# rodentdbs.net
KiCad netlist of a schematic drawn in EAGLE
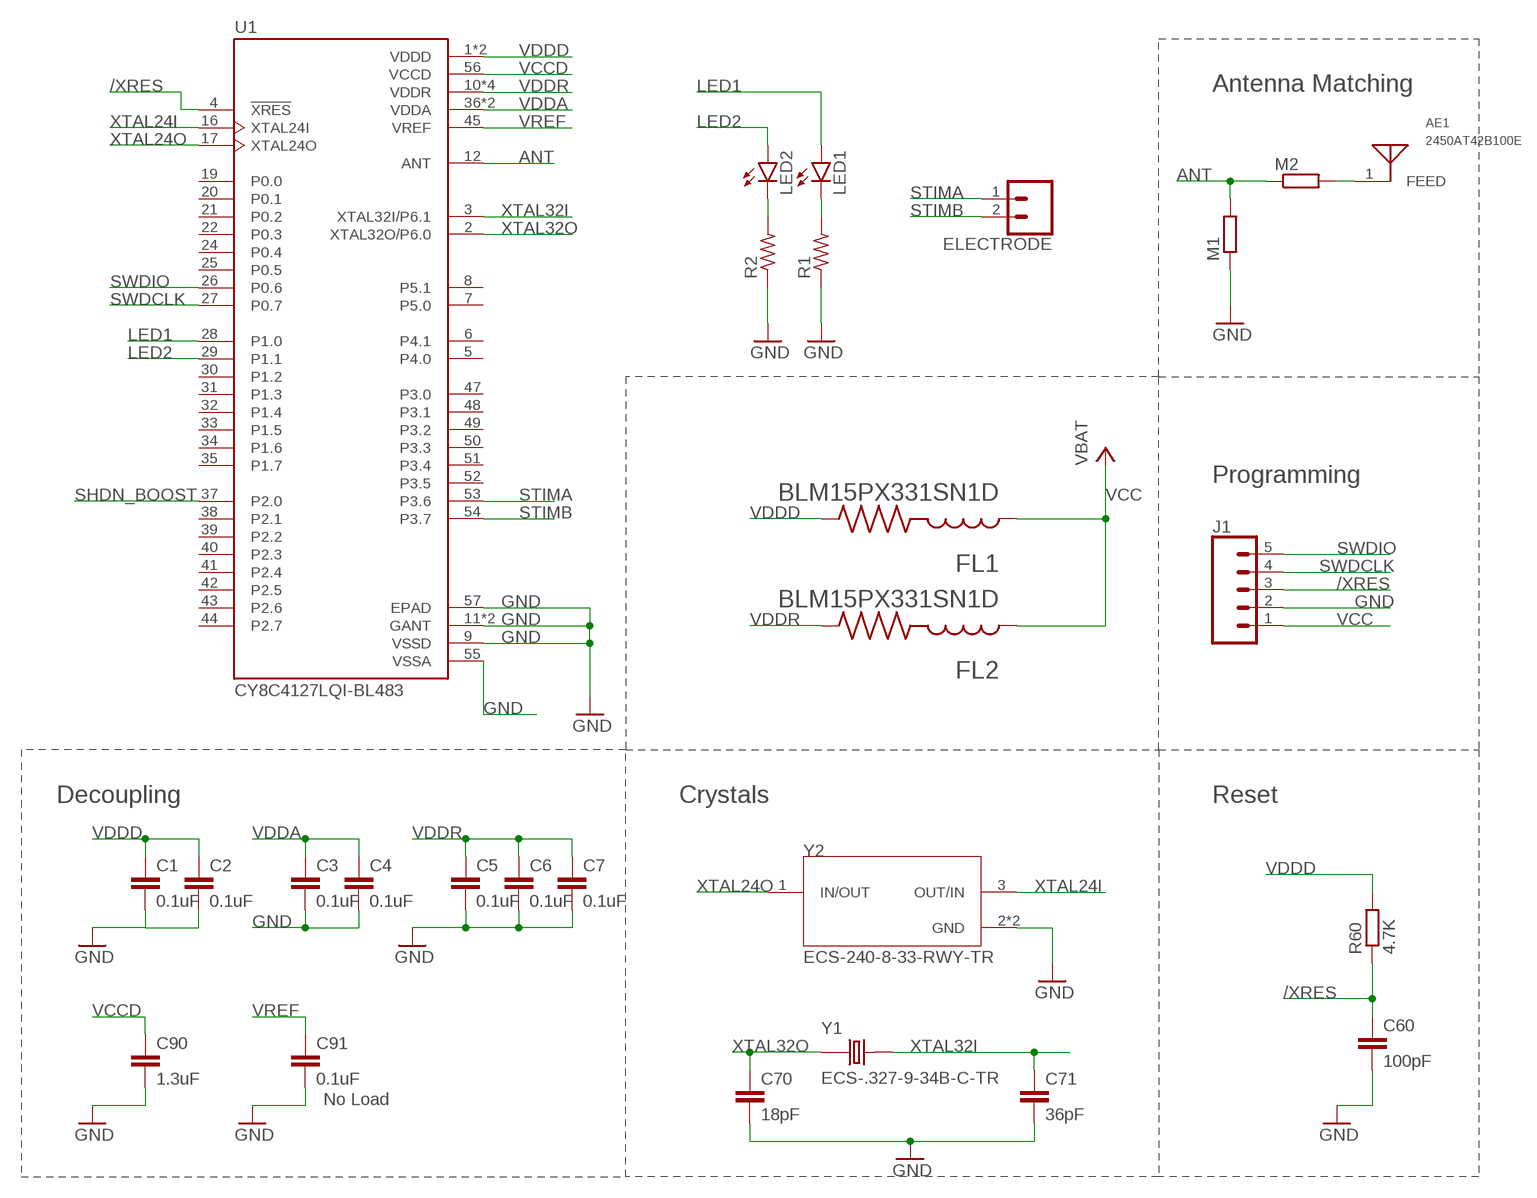
[diagram p0: schematic, sheet 1]
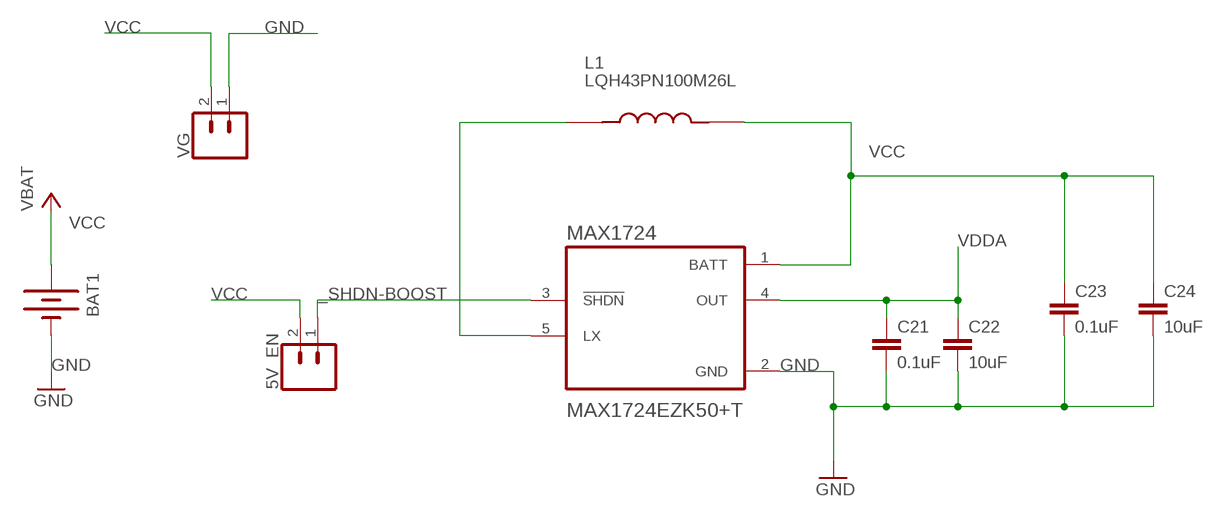
[diagram p1: schematic, sheet 2]

(export (version "E")
  (design (tool "Eeschema 10.0.6"))
  (components
    (comp (ref "AE1")
      (value "2450AT42B100E")
      (footprint "eagle-import:XCVR_2450AT42B100E")
      (fields (field (name "DIGI-KEY_PART_NUMBER") "712-1008-2-ND") (field (name "MF") "Johanson Technology"))
      (libsource (lib "eagle-import") (part "2450AT42B100E"))
    )
    (comp (ref "C1")
      (value "0.1uF")
      (footprint "eagle-import:C0402")
      (libsource (lib "eagle-import") (part "C-EUC0402"))
    )
    (comp (ref "C2")
      (value "0.1uF")
      (footprint "eagle-import:C0402")
      (libsource (lib "eagle-import") (part "C-EUC0402"))
    )
    (comp (ref "C3")
      (value "0.1uF")
      (footprint "eagle-import:C0402")
      (libsource (lib "eagle-import") (part "C-EUC0402"))
    )
    (comp (ref "C4")
      (value "0.1uF")
      (footprint "eagle-import:C0402")
      (libsource (lib "eagle-import") (part "C-EUC0402"))
    )
    (comp (ref "C5")
      (value "0.1uF")
      (footprint "eagle-import:C0402")
      (libsource (lib "eagle-import") (part "C-EUC0402"))
    )
    (comp (ref "C6")
      (value "0.1uF")
      (footprint "eagle-import:C0402")
      (libsource (lib "eagle-import") (part "C-EUC0402"))
    )
    (comp (ref "C7")
      (value "0.1uF")
      (footprint "eagle-import:C0402")
      (libsource (lib "eagle-import") (part "C-EUC0402"))
    )
    (comp (ref "C60")
      (value "100pF")
      (footprint "eagle-import:C0402")
      (libsource (lib "eagle-import") (part "C-EUC0402"))
    )
    (comp (ref "C70")
      (value "18pF")
      (footprint "eagle-import:C0402")
      (libsource (lib "eagle-import") (part "C-EUC0402"))
    )
    (comp (ref "C71")
      (value "36pF")
      (footprint "eagle-import:C0402")
      (libsource (lib "eagle-import") (part "C-EUC0402"))
    )
    (comp (ref "C90")
      (value "1.3uF")
      (footprint "eagle-import:C0402")
      (libsource (lib "eagle-import") (part "C-EUC0402"))
    )
    (comp (ref "C91")
      (value "0.1uF")
      (footprint "eagle-import:C0402")
      (libsource (lib "eagle-import") (part "C-EUC0402"))
    )
    (comp (ref "ELECTRODE")
      (value "CONN_02")
      (footprint "eagle-import:1X02")
      (libsource (lib "eagle-import") (part "CONN_02"))
    )
    (comp (ref "FL1")
      (value "BLM15PX331SN1D")
      (footprint "eagle-import:BEADC1005X55N")
      (fields (field (name "DIGI-KEY_PART_NUMBER") "490-11022-2-ND") (field (name "MF") "Murata Electronics"))
      (libsource (lib "eagle-import") (part "BLM15PX331SN1D"))
    )
    (comp (ref "FL2")
      (value "BLM15PX331SN1D")
      (footprint "eagle-import:BEADC1005X55N")
      (fields (field (name "DIGI-KEY_PART_NUMBER") "490-11022-2-ND") (field (name "MF") "Murata Electronics"))
      (libsource (lib "eagle-import") (part "BLM15PX331SN1D"))
    )
    (comp (ref "J1")
      (value "CONN_05LOCK")
      (footprint "eagle-import:1X05_LOCK")
      (libsource (lib "eagle-import") (part "CONN_05LOCK"))
    )
    (comp (ref "LED1")
      (value "LEDSML0603")
      (footprint "eagle-import:SML0603")
      (libsource (lib "eagle-import") (part "LEDSML0603"))
    )
    (comp (ref "LED2")
      (value "LEDSML0603")
      (footprint "eagle-import:SML0603")
      (libsource (lib "eagle-import") (part "LEDSML0603"))
    )
    (comp (ref "M1")
      (value "R-EU_R0402")
      (footprint "eagle-import:R0402")
      (libsource (lib "eagle-import") (part "R-EU_R0402"))
    )
    (comp (ref "M2")
      (value "R-EU_R0402")
      (footprint "eagle-import:R0402")
      (libsource (lib "eagle-import") (part "R-EU_R0402"))
    )
    (comp (ref "R1")
      (value "R-US_R0402")
      (footprint "eagle-import:R0402")
      (libsource (lib "eagle-import") (part "R-US_R0402"))
    )
    (comp (ref "R2")
      (value "R-US_R0402")
      (footprint "eagle-import:R0402")
      (libsource (lib "eagle-import") (part "R-US_R0402"))
    )
    (comp (ref "R60")
      (value "4.7K")
      (footprint "eagle-import:R0402")
      (libsource (lib "eagle-import") (part "R-EU_R0402"))
    )
    (comp (ref "U1")
      (value "CY8C4127LQI-BL483")
      (footprint "eagle-import:QFN40P700X700X60-57N")
      (libsource (lib "eagle-import") (part "CY8C4127LQI-BL483"))
    )
    (comp (ref "Y1")
      (value "ECS-.327-9-34B-C-TR")
      (footprint "eagle-import:XTAL_ECS-.327-9-34B-C-TR")
      (fields (field (name "DIGI-KEY_PART_NUMBER") "XC1949TR-ND") (field (name "MF") "ECS Inc."))
      (libsource (lib "eagle-import") (part "ECS-.327-9-34B-C-TR"))
    )
    (comp (ref "Y2")
      (value "ECS-240-8-33-RWY-TR")
      (footprint "eagle-import:XTAL_ECS-240-8-33-RWY-TR")
      (fields (field (name "DIGI-KEY_PART_NUMBER") "XC2946TR-ND") (field (name "MF") "ECS Inc."))
      (libsource (lib "eagle-import") (part "ECS-240-8-33-RWY-TR"))
    )
    (comp (ref "5V_EN")
      (value "CONN_02")
      (footprint "eagle-import:1X02")
      (libsource (lib "eagle-import") (part "CONN_02"))
    )
    (comp (ref "BAT1")
      (value "BATTERYBU2032SM")
      (footprint "eagle-import:BU2032SM")
      (libsource (lib "eagle-import") (part "BATTERYBU2032SM"))
    )
    (comp (ref "C21")
      (value "0.1uF")
      (footprint "eagle-import:C0402")
      (libsource (lib "eagle-import") (part "C-EUC0402"))
    )
    (comp (ref "C22")
      (value "10uF")
      (footprint "eagle-import:C0603")
      (libsource (lib "eagle-import") (part "C-EUC0603"))
    )
    (comp (ref "C23")
      (value "0.1uF")
      (footprint "eagle-import:C0402")
      (libsource (lib "eagle-import") (part "C-EUC0402"))
    )
    (comp (ref "C24")
      (value "10uF")
      (footprint "eagle-import:C0603")
      (libsource (lib "eagle-import") (part "C-EUC0603"))
    )
    (comp (ref "L1")
      (value "LQH43PN100M26L")
      (footprint "eagle-import:IND_LQH43PN100M26L")
      (fields (field (name "DIGI-KEY_PART_NUMBER") "490-12780-1-ND") (field (name "MF") "Murata"))
      (libsource (lib "eagle-import") (part "LQH43PN100M26L"))
    )
    (comp (ref "MAX1724")
      (value "MAX1724EZK50+T")
      (footprint "eagle-import:SOT95P275X110-5N")
      (fields
        (field (name "DIGI-KEY_PART_NUMBER") "MAX1724EZK50+TCT-ND")
        (field (name "MF") "Maxim Integrated")
      )
      (libsource (lib "eagle-import") (part "MAX1724EZK50+T"))
    )
    (comp (ref "VG")
      (value "CONN_02")
      (footprint "eagle-import:1X02")
      (libsource (lib "eagle-import") (part "CONN_02"))
    )
  )
  (nets
    (net (code "1") (name "ANT") (class "Default")
      (node (ref "M1") (pin "2") (pinfunction "2_2") (pintype "passive"))
      (node (ref "M2") (pin "1") (pinfunction "1_1") (pintype "passive"))
      (node (ref "U1") (pin "12") (pinfunction "ANT_12") (pintype "bidirectional"))
    )
    (net (code "2") (name "GND") (class "Default")
      (node (ref "BAT1") (pin "P$2") (pinfunction "-_P$2") (pintype "power_in"))
      (node (ref "C1") (pin "2") (pinfunction "2_2") (pintype "passive"))
      (node (ref "C2") (pin "2") (pinfunction "2_2") (pintype "passive"))
      (node (ref "C21") (pin "2") (pinfunction "2_2") (pintype "passive"))
      (node (ref "C22") (pin "2") (pinfunction "2_2") (pintype "passive"))
      (node (ref "C23") (pin "2") (pinfunction "2_2") (pintype "passive"))
      (node (ref "C24") (pin "2") (pinfunction "2_2") (pintype "passive"))
      (node (ref "C3") (pin "2") (pinfunction "2_2") (pintype "passive"))
      (node (ref "C4") (pin "2") (pinfunction "2_2") (pintype "passive"))
      (node (ref "C5") (pin "2") (pinfunction "2_2") (pintype "passive"))
      (node (ref "C6") (pin "2") (pinfunction "2_2") (pintype "passive"))
      (node (ref "C60") (pin "2") (pinfunction "2_2") (pintype "passive"))
      (node (ref "C7") (pin "2") (pinfunction "2_2") (pintype "passive"))
      (node (ref "C70") (pin "2") (pinfunction "2_2") (pintype "passive"))
      (node (ref "C71") (pin "2") (pinfunction "2_2") (pintype "passive"))
      (node (ref "C90") (pin "2") (pinfunction "2_2") (pintype "passive"))
      (node (ref "C91") (pin "2") (pinfunction "2_2") (pintype "passive"))
      (node (ref "J1") (pin "2") (pinfunction "2_2") (pintype "passive"))
      (node (ref "M1") (pin "1") (pinfunction "1_1") (pintype "passive"))
      (node (ref "MAX1724") (pin "2") (pinfunction "GND_2") (pintype "power_in"))
      (node (ref "R1") (pin "1") (pinfunction "1_1") (pintype "passive"))
      (node (ref "R2") (pin "1") (pinfunction "1_1") (pintype "passive"))
      (node (ref "U1") (pin "11") (pinfunction "GANT_11") (pintype "power_in"))
      (node (ref "U1") (pin "13") (pinfunction "GANT_13") (pintype "power_in"))
      (node (ref "U1") (pin "55") (pinfunction "VSSA_55") (pintype "power_in"))
      (node (ref "U1") (pin "57") (pinfunction "EPAD_57") (pintype "power_in"))
      (node (ref "U1") (pin "9") (pinfunction "VSSD_9") (pintype "power_in"))
      (node (ref "VG") (pin "1") (pinfunction "1_1") (pintype "passive"))
      (node (ref "Y2") (pin "2") (pinfunction "GND_2") (pintype "power_in"))
      (node (ref "Y2") (pin "4") (pinfunction "GND_4") (pintype "power_in"))
    )
    (net (code "3") (name "LED1") (class "Default")
      (node (ref "LED1") (pin "A") (pinfunction "A_A") (pintype "passive"))
      (node (ref "U1") (pin "28") (pinfunction "P1.0_28") (pintype "bidirectional"))
    )
    (net (code "4") (name "LED2") (class "Default")
      (node (ref "LED2") (pin "A") (pinfunction "A_A") (pintype "passive"))
      (node (ref "U1") (pin "29") (pinfunction "P1.1_29") (pintype "bidirectional"))
    )
    (net (code "5") (name "Net-(AE1-FEED)") (class "Default")
      (node (ref "AE1") (pin "1") (pinfunction "FEED_1") (pintype "passive"))
      (node (ref "M2") (pin "2") (pinfunction "2_2") (pintype "passive"))
    )
    (net (code "6") (name "Net-(LED1-PadC)") (class "Default")
      (node (ref "LED1") (pin "C") (pinfunction "C_C") (pintype "passive"))
      (node (ref "R1") (pin "2") (pinfunction "2_2") (pintype "passive"))
    )
    (net (code "7") (name "Net-(LED2-PadC)") (class "Default")
      (node (ref "LED2") (pin "C") (pinfunction "C_C") (pintype "passive"))
      (node (ref "R2") (pin "2") (pinfunction "2_2") (pintype "passive"))
    )
    (net (code "8") (name "Net-(MAX1724-LX)") (class "Default")
      (node (ref "L1") (pin "1") (pinfunction "1_1") (pintype "passive"))
      (node (ref "MAX1724") (pin "5") (pinfunction "LX_5") (pintype "bidirectional"))
    )
    (net (code "9") (name "SHDN_BOOST") (class "Default")
      (node (ref "U1") (pin "37") (pinfunction "P2.0_37") (pintype "bidirectional"))
    )
    (net (code "10") (name "STIMA") (class "Default")
      (node (ref "ELECTRODE") (pin "1") (pinfunction "1_1") (pintype "passive"))
      (node (ref "U1") (pin "53") (pinfunction "P3.6_53") (pintype "bidirectional"))
    )
    (net (code "11") (name "STIMB") (class "Default")
      (node (ref "ELECTRODE") (pin "2") (pinfunction "2_2") (pintype "passive"))
      (node (ref "U1") (pin "54") (pinfunction "P3.7_54") (pintype "bidirectional"))
    )
    (net (code "12") (name "SWDCLK") (class "Default")
      (node (ref "J1") (pin "4") (pinfunction "4_4") (pintype "passive"))
      (node (ref "U1") (pin "27") (pinfunction "P0.7_27") (pintype "bidirectional"))
    )
    (net (code "13") (name "SWDIO") (class "Default")
      (node (ref "J1") (pin "5") (pinfunction "5_5") (pintype "passive"))
      (node (ref "U1") (pin "26") (pinfunction "P0.6_26") (pintype "bidirectional"))
    )
    (net (code "14") (name "VCC") (class "Default")
      (node (ref "5V_EN") (pin "2") (pinfunction "2_2") (pintype "passive"))
      (node (ref "BAT1") (pin "P$1") (pinfunction "+_P$1") (pintype "power_in"))
      (node (ref "C23") (pin "1") (pinfunction "1_1") (pintype "passive"))
      (node (ref "C24") (pin "1") (pinfunction "1_1") (pintype "passive"))
      (node (ref "FL1") (pin "1") (pinfunction "1_1") (pintype "passive"))
      (node (ref "FL2") (pin "1") (pinfunction "1_1") (pintype "passive"))
      (node (ref "J1") (pin "1") (pinfunction "1_1") (pintype "passive"))
      (node (ref "L1") (pin "2") (pinfunction "2_2") (pintype "passive"))
      (node (ref "MAX1724") (pin "1") (pinfunction "BATT_1") (pintype "power_in"))
      (node (ref "VG") (pin "2") (pinfunction "2_2") (pintype "passive"))
    )
    (net (code "15") (name "VCCD") (class "Default")
      (node (ref "C90") (pin "1") (pinfunction "1_1") (pintype "passive"))
      (node (ref "U1") (pin "56") (pinfunction "VCCD_56") (pintype "power_in"))
    )
    (net (code "16") (name "VDDA") (class "Default")
      (node (ref "C21") (pin "1") (pinfunction "1_1") (pintype "passive"))
      (node (ref "C22") (pin "1") (pinfunction "1_1") (pintype "passive"))
      (node (ref "C3") (pin "1") (pinfunction "1_1") (pintype "passive"))
      (node (ref "C4") (pin "1") (pinfunction "1_1") (pintype "passive"))
      (node (ref "MAX1724") (pin "4") (pinfunction "OUT_4") (pintype "output"))
      (node (ref "U1") (pin "36") (pinfunction "VDDA_36") (pintype "power_in"))
      (node (ref "U1") (pin "46") (pinfunction "VDDA_46") (pintype "power_in"))
    )
    (net (code "17") (name "VDDD") (class "Default")
      (node (ref "C1") (pin "1") (pinfunction "1_1") (pintype "passive"))
      (node (ref "C2") (pin "1") (pinfunction "1_1") (pintype "passive"))
      (node (ref "FL1") (pin "2") (pinfunction "2_2") (pintype "passive"))
      (node (ref "R60") (pin "2") (pinfunction "2_2") (pintype "passive"))
      (node (ref "U1") (pin "1") (pinfunction "VDDD_1") (pintype "power_in"))
      (node (ref "U1") (pin "23") (pinfunction "VDDD_23") (pintype "power_in"))
    )
    (net (code "18") (name "VDDR") (class "Default")
      (node (ref "C5") (pin "1") (pinfunction "1_1") (pintype "passive"))
      (node (ref "C6") (pin "1") (pinfunction "1_1") (pintype "passive"))
      (node (ref "C7") (pin "1") (pinfunction "1_1") (pintype "passive"))
      (node (ref "FL2") (pin "2") (pinfunction "2_2") (pintype "passive"))
      (node (ref "U1") (pin "10") (pinfunction "VDDR_10") (pintype "power_in"))
      (node (ref "U1") (pin "14") (pinfunction "VDDR_14") (pintype "power_in"))
      (node (ref "U1") (pin "15") (pinfunction "VDDR_15") (pintype "power_in"))
      (node (ref "U1") (pin "18") (pinfunction "VDDR_18") (pintype "power_in"))
    )
    (net (code "19") (name "VREF") (class "Default")
      (node (ref "C91") (pin "1") (pinfunction "1_1") (pintype "passive"))
      (node (ref "U1") (pin "45") (pinfunction "VREF_45") (pintype "power_in"))
    )
    (net (code "20") (name "XTAL24I") (class "Default")
      (node (ref "U1") (pin "16") (pinfunction "XTAL24I_16") (pintype "input"))
      (node (ref "Y2") (pin "3") (pinfunction "OUT/IN_3") (pintype "bidirectional"))
    )
    (net (code "21") (name "XTAL24O") (class "Default")
      (node (ref "U1") (pin "17") (pinfunction "XTAL24O_17") (pintype "input"))
      (node (ref "Y2") (pin "1") (pinfunction "IN/OUT_1") (pintype "bidirectional"))
    )
    (net (code "22") (name "XTAL32I") (class "Default")
      (node (ref "C71") (pin "1") (pinfunction "1_1") (pintype "passive"))
      (node (ref "U1") (pin "3") (pinfunction "XTAL32I/P6.1_3") (pintype "bidirectional"))
      (node (ref "Y1") (pin "2") (pinfunction "2_2") (pintype "passive"))
    )
    (net (code "23") (name "XTAL32O") (class "Default")
      (node (ref "C70") (pin "1") (pinfunction "1_1") (pintype "passive"))
      (node (ref "U1") (pin "2") (pinfunction "XTAL32O/P6.0_2") (pintype "bidirectional"))
      (node (ref "Y1") (pin "1") (pinfunction "1_1") (pintype "passive"))
    )
    (net (code "24") (name "_SHDN-BOOST") (class "Default")
      (node (ref "5V_EN") (pin "1") (pinfunction "1_1") (pintype "passive"))
      (node (ref "MAX1724") (pin "3") (pinfunction "~{SHDN}_3") (pintype "input"))
    )
    (net (code "25") (name "unconnected-(U1-P0.0-Pad19)") (class "Default")
      (node (ref "U1") (pin "19") (pinfunction "P0.0_19") (pintype "bidirectional"))
    )
    (net (code "26") (name "unconnected-(U1-P0.1-Pad20)") (class "Default")
      (node (ref "U1") (pin "20") (pinfunction "P0.1_20") (pintype "bidirectional"))
    )
    (net (code "27") (name "unconnected-(U1-P0.2-Pad21)") (class "Default")
      (node (ref "U1") (pin "21") (pinfunction "P0.2_21") (pintype "bidirectional"))
    )
    (net (code "28") (name "unconnected-(U1-P0.3-Pad22)") (class "Default")
      (node (ref "U1") (pin "22") (pinfunction "P0.3_22") (pintype "bidirectional"))
    )
    (net (code "29") (name "unconnected-(U1-P0.4-Pad24)") (class "Default")
      (node (ref "U1") (pin "24") (pinfunction "P0.4_24") (pintype "bidirectional"))
    )
    (net (code "30") (name "unconnected-(U1-P0.5-Pad25)") (class "Default")
      (node (ref "U1") (pin "25") (pinfunction "P0.5_25") (pintype "bidirectional"))
    )
    (net (code "31") (name "unconnected-(U1-P1.2-Pad30)") (class "Default")
      (node (ref "U1") (pin "30") (pinfunction "P1.2_30") (pintype "bidirectional"))
    )
    (net (code "32") (name "unconnected-(U1-P1.3-Pad31)") (class "Default")
      (node (ref "U1") (pin "31") (pinfunction "P1.3_31") (pintype "bidirectional"))
    )
    (net (code "33") (name "unconnected-(U1-P1.4-Pad32)") (class "Default")
      (node (ref "U1") (pin "32") (pinfunction "P1.4_32") (pintype "bidirectional"))
    )
    (net (code "34") (name "unconnected-(U1-P1.5-Pad33)") (class "Default")
      (node (ref "U1") (pin "33") (pinfunction "P1.5_33") (pintype "bidirectional"))
    )
    (net (code "35") (name "unconnected-(U1-P1.6-Pad34)") (class "Default")
      (node (ref "U1") (pin "34") (pinfunction "P1.6_34") (pintype "bidirectional"))
    )
    (net (code "36") (name "unconnected-(U1-P1.7-Pad35)") (class "Default")
      (node (ref "U1") (pin "35") (pinfunction "P1.7_35") (pintype "bidirectional"))
    )
    (net (code "37") (name "unconnected-(U1-P2.1-Pad38)") (class "Default")
      (node (ref "U1") (pin "38") (pinfunction "P2.1_38") (pintype "bidirectional"))
    )
    (net (code "38") (name "unconnected-(U1-P2.2-Pad39)") (class "Default")
      (node (ref "U1") (pin "39") (pinfunction "P2.2_39") (pintype "bidirectional"))
    )
    (net (code "39") (name "unconnected-(U1-P2.3-Pad40)") (class "Default")
      (node (ref "U1") (pin "40") (pinfunction "P2.3_40") (pintype "bidirectional"))
    )
    (net (code "40") (name "unconnected-(U1-P2.4-Pad41)") (class "Default")
      (node (ref "U1") (pin "41") (pinfunction "P2.4_41") (pintype "bidirectional"))
    )
    (net (code "41") (name "unconnected-(U1-P2.5-Pad42)") (class "Default")
      (node (ref "U1") (pin "42") (pinfunction "P2.5_42") (pintype "bidirectional"))
    )
    (net (code "42") (name "unconnected-(U1-P2.6-Pad43)") (class "Default")
      (node (ref "U1") (pin "43") (pinfunction "P2.6_43") (pintype "bidirectional"))
    )
    (net (code "43") (name "unconnected-(U1-P2.7-Pad44)") (class "Default")
      (node (ref "U1") (pin "44") (pinfunction "P2.7_44") (pintype "bidirectional"))
    )
    (net (code "44") (name "unconnected-(U1-P3.0-Pad47)") (class "Default")
      (node (ref "U1") (pin "47") (pinfunction "P3.0_47") (pintype "bidirectional"))
    )
    (net (code "45") (name "unconnected-(U1-P3.1-Pad48)") (class "Default")
      (node (ref "U1") (pin "48") (pinfunction "P3.1_48") (pintype "bidirectional"))
    )
    (net (code "46") (name "unconnected-(U1-P3.2-Pad49)") (class "Default")
      (node (ref "U1") (pin "49") (pinfunction "P3.2_49") (pintype "bidirectional"))
    )
    (net (code "47") (name "unconnected-(U1-P3.3-Pad50)") (class "Default")
      (node (ref "U1") (pin "50") (pinfunction "P3.3_50") (pintype "bidirectional"))
    )
    (net (code "48") (name "unconnected-(U1-P3.4-Pad51)") (class "Default")
      (node (ref "U1") (pin "51") (pinfunction "P3.4_51") (pintype "bidirectional"))
    )
    (net (code "49") (name "unconnected-(U1-P3.5-Pad52)") (class "Default")
      (node (ref "U1") (pin "52") (pinfunction "P3.5_52") (pintype "bidirectional"))
    )
    (net (code "50") (name "unconnected-(U1-P4.0-Pad5)") (class "Default")
      (node (ref "U1") (pin "5") (pinfunction "P4.0_5") (pintype "bidirectional"))
    )
    (net (code "51") (name "unconnected-(U1-P4.1-Pad6)") (class "Default")
      (node (ref "U1") (pin "6") (pinfunction "P4.1_6") (pintype "bidirectional"))
    )
    (net (code "52") (name "unconnected-(U1-P5.0-Pad7)") (class "Default")
      (node (ref "U1") (pin "7") (pinfunction "P5.0_7") (pintype "bidirectional"))
    )
    (net (code "53") (name "unconnected-(U1-P5.1-Pad8)") (class "Default")
      (node (ref "U1") (pin "8") (pinfunction "P5.1_8") (pintype "bidirectional"))
    )
    (net (code "54") (name "{slash}XRES") (class "Default")
      (node (ref "C60") (pin "1") (pinfunction "1_1") (pintype "passive"))
      (node (ref "J1") (pin "3") (pinfunction "3_3") (pintype "passive"))
      (node (ref "R60") (pin "1") (pinfunction "1_1") (pintype "passive"))
      (node (ref "U1") (pin "4") (pinfunction "~{XRES}_4") (pintype "input"))
    )
  )
)
